# six4mix.net
KiCad netlist of a schematic drawn in EAGLE
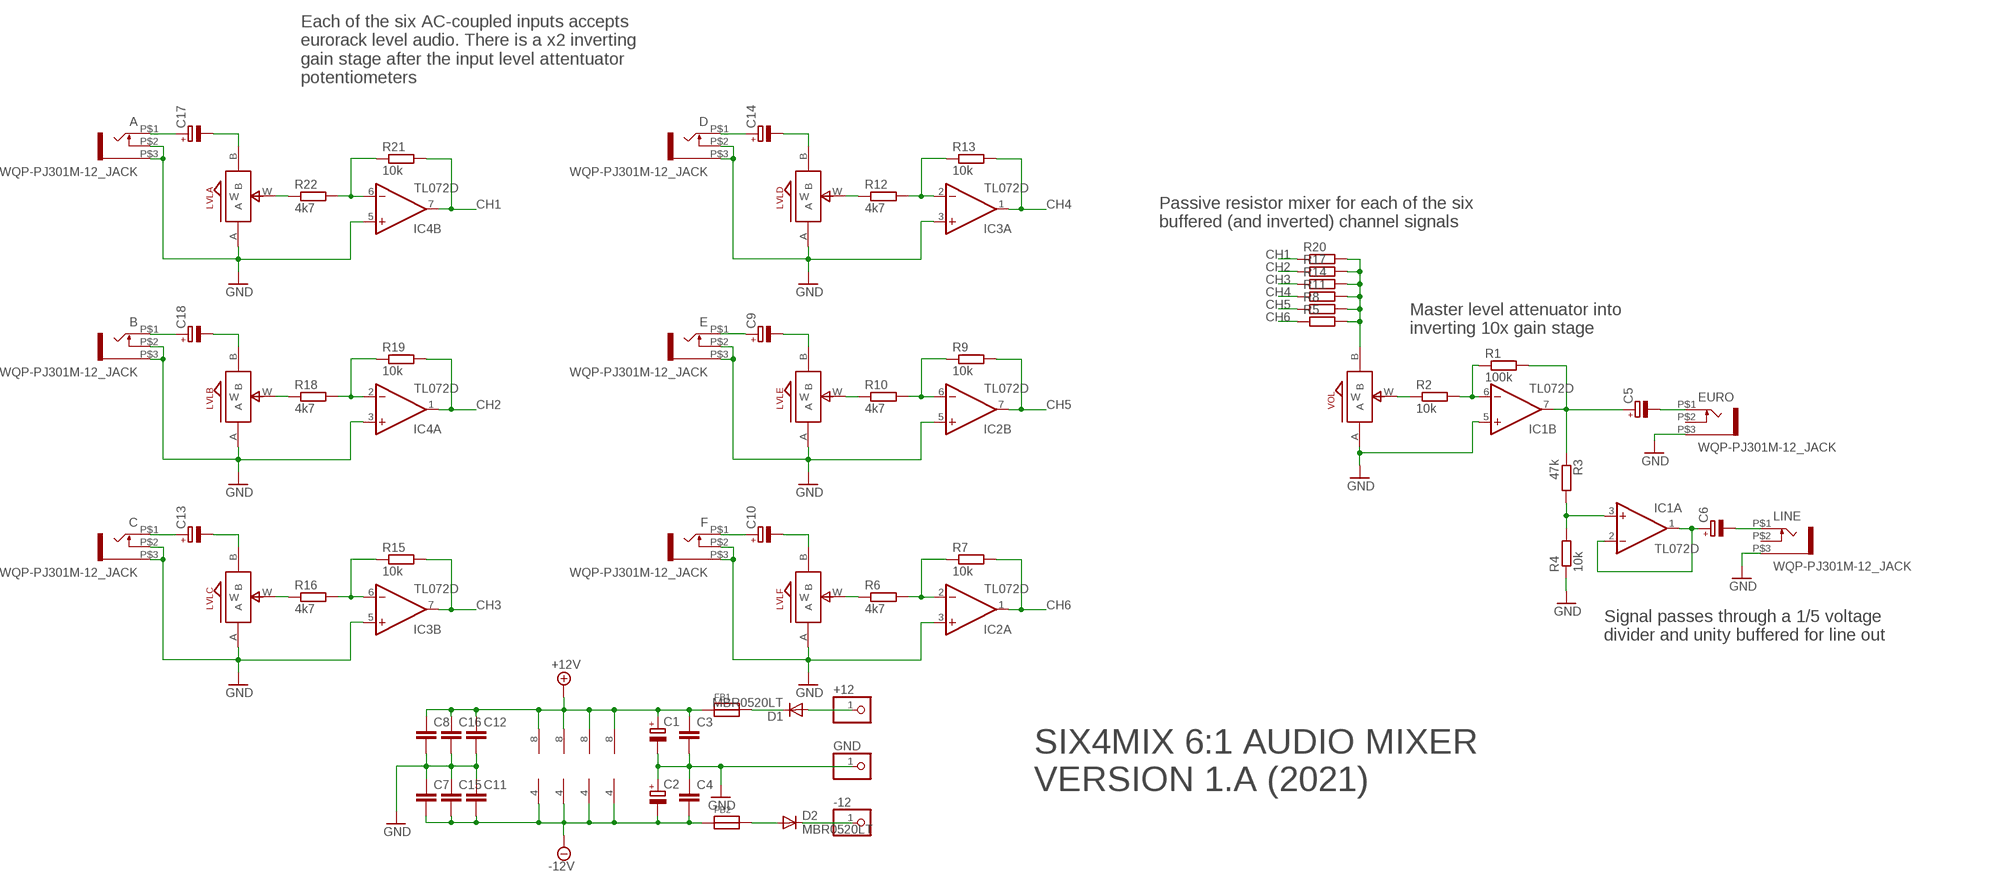
[diagram p0: schematic, sheet 1]

(export (version "E")
  (design (tool "Eeschema 10.0.6"))
  (components
    (comp (ref "+12")
      (value "PINHD-1X1")
      (footprint "eagle-import:1X01")
      (libsource (lib "eagle-import") (part "PINHD-1X1"))
    )
    (comp (ref "-12")
      (value "PINHD-1X1")
      (footprint "eagle-import:1X01")
      (libsource (lib "eagle-import") (part "PINHD-1X1"))
    )
    (comp (ref "A")
      (value "WQP-PJ301M-12_JACK")
      (footprint "eagle-import:WQP-PJ301M-12_JACK")
      (libsource (lib "eagle-import") (part "WQP-PJ301M-12_JACK"))
    )
    (comp (ref "B")
      (value "WQP-PJ301M-12_JACK")
      (footprint "eagle-import:WQP-PJ301M-12_JACK")
      (libsource (lib "eagle-import") (part "WQP-PJ301M-12_JACK"))
    )
    (comp (ref "C")
      (value "WQP-PJ301M-12_JACK")
      (footprint "eagle-import:WQP-PJ301M-12_JACK")
      (libsource (lib "eagle-import") (part "WQP-PJ301M-12_JACK"))
    )
    (comp (ref "C1")
      (value "CPOL-EUE2-4")
      (footprint "eagle-import:E2-4")
      (libsource (lib "eagle-import") (part "CPOL-EUE2-4"))
    )
    (comp (ref "C2")
      (value "CPOL-EUE2-4")
      (footprint "eagle-import:E2-4")
      (libsource (lib "eagle-import") (part "CPOL-EUE2-4"))
    )
    (comp (ref "C3")
      (value "C-EUC0805")
      (footprint "eagle-import:C0805")
      (libsource (lib "eagle-import") (part "C-EUC0805"))
    )
    (comp (ref "C4")
      (value "C-EUC0805")
      (footprint "eagle-import:C0805")
      (libsource (lib "eagle-import") (part "C-EUC0805"))
    )
    (comp (ref "C5")
      (value "CPOL-EUE2-4")
      (footprint "eagle-import:E2-4")
      (libsource (lib "eagle-import") (part "CPOL-EUE2-4"))
    )
    (comp (ref "C6")
      (value "CPOL-EUE2-4")
      (footprint "eagle-import:E2-4")
      (libsource (lib "eagle-import") (part "CPOL-EUE2-4"))
    )
    (comp (ref "C7")
      (value "C-EUC0805")
      (footprint "eagle-import:C0805")
      (libsource (lib "eagle-import") (part "C-EUC0805"))
    )
    (comp (ref "C8")
      (value "C-EUC0805")
      (footprint "eagle-import:C0805")
      (libsource (lib "eagle-import") (part "C-EUC0805"))
    )
    (comp (ref "C9")
      (value "CPOL-EUE2-4")
      (footprint "eagle-import:E2-4")
      (libsource (lib "eagle-import") (part "CPOL-EUE2-4"))
    )
    (comp (ref "C10")
      (value "CPOL-EUE2-4")
      (footprint "eagle-import:E2-4")
      (libsource (lib "eagle-import") (part "CPOL-EUE2-4"))
    )
    (comp (ref "C11")
      (value "C-EUC0805")
      (footprint "eagle-import:C0805")
      (libsource (lib "eagle-import") (part "C-EUC0805"))
    )
    (comp (ref "C12")
      (value "C-EUC0805")
      (footprint "eagle-import:C0805")
      (libsource (lib "eagle-import") (part "C-EUC0805"))
    )
    (comp (ref "C13")
      (value "CPOL-EUE2-4")
      (footprint "eagle-import:E2-4")
      (libsource (lib "eagle-import") (part "CPOL-EUE2-4"))
    )
    (comp (ref "C14")
      (value "CPOL-EUE2-4")
      (footprint "eagle-import:E2-4")
      (libsource (lib "eagle-import") (part "CPOL-EUE2-4"))
    )
    (comp (ref "C15")
      (value "C-EUC0805")
      (footprint "eagle-import:C0805")
      (libsource (lib "eagle-import") (part "C-EUC0805"))
    )
    (comp (ref "C16")
      (value "C-EUC0805")
      (footprint "eagle-import:C0805")
      (libsource (lib "eagle-import") (part "C-EUC0805"))
    )
    (comp (ref "C17")
      (value "CPOL-EUE2-4")
      (footprint "eagle-import:E2-4")
      (libsource (lib "eagle-import") (part "CPOL-EUE2-4"))
    )
    (comp (ref "C18")
      (value "CPOL-EUE2-4")
      (footprint "eagle-import:E2-4")
      (libsource (lib "eagle-import") (part "CPOL-EUE2-4"))
    )
    (comp (ref "D")
      (value "WQP-PJ301M-12_JACK")
      (footprint "eagle-import:WQP-PJ301M-12_JACK")
      (libsource (lib "eagle-import") (part "WQP-PJ301M-12_JACK"))
    )
    (comp (ref "D1")
      (value "MBR0520LT")
      (footprint "eagle-import:SOD123")
      (libsource (lib "eagle-import") (part "MBR0520LT"))
    )
    (comp (ref "D2")
      (value "MBR0520LT")
      (footprint "eagle-import:SOD123")
      (libsource (lib "eagle-import") (part "MBR0520LT"))
    )
    (comp (ref "E")
      (value "WQP-PJ301M-12_JACK")
      (footprint "eagle-import:WQP-PJ301M-12_JACK")
      (libsource (lib "eagle-import") (part "WQP-PJ301M-12_JACK"))
    )
    (comp (ref "EURO")
      (value "WQP-PJ301M-12_JACK")
      (footprint "eagle-import:WQP-PJ301M-12_JACK")
      (libsource (lib "eagle-import") (part "WQP-PJ301M-12_JACK"))
    )
    (comp (ref "F")
      (value "WQP-PJ301M-12_JACK")
      (footprint "eagle-import:WQP-PJ301M-12_JACK")
      (libsource (lib "eagle-import") (part "WQP-PJ301M-12_JACK"))
    )
    (comp (ref "FB1")
      (value "FERRITE")
      (footprint "eagle-import:0603")
      (libsource (lib "eagle-import") (part "FERRITE"))
    )
    (comp (ref "FB2")
      (value "FERRITE")
      (footprint "eagle-import:0603")
      (libsource (lib "eagle-import") (part "FERRITE"))
    )
    (comp (ref "GND")
      (value "PINHD-1X1")
      (footprint "eagle-import:1X01")
      (libsource (lib "eagle-import") (part "PINHD-1X1"))
    )
    (comp (ref "IC1")
      (value "TL072D")
      (footprint "eagle-import:SO08")
      (libsource (lib "eagle-import") (part "TL072D"))
    )
    (comp (ref "IC2")
      (value "TL072D")
      (footprint "eagle-import:SO08")
      (libsource (lib "eagle-import") (part "TL072D"))
    )
    (comp (ref "IC3")
      (value "TL072D")
      (footprint "eagle-import:SO08")
      (libsource (lib "eagle-import") (part "TL072D"))
    )
    (comp (ref "IC4")
      (value "TL072D")
      (footprint "eagle-import:SO08")
      (libsource (lib "eagle-import") (part "TL072D"))
    )
    (comp (ref "LINE")
      (value "WQP-PJ301M-12_JACK")
      (footprint "eagle-import:WQP-PJ301M-12_JACK")
      (libsource (lib "eagle-import") (part "WQP-PJ301M-12_JACK"))
    )
    (comp (ref "LVLA")
      (value "ALPS_POT_SMALL")
      (footprint "eagle-import:SMALL_ALPS_POT")
      (libsource (lib "eagle-import") (part "ALPS_POT_SMALL"))
    )
    (comp (ref "LVLB")
      (value "ALPS_POT_SMALL")
      (footprint "eagle-import:SMALL_ALPS_POT")
      (libsource (lib "eagle-import") (part "ALPS_POT_SMALL"))
    )
    (comp (ref "LVLC")
      (value "ALPS_POT_SMALL")
      (footprint "eagle-import:SMALL_ALPS_POT")
      (libsource (lib "eagle-import") (part "ALPS_POT_SMALL"))
    )
    (comp (ref "LVLD")
      (value "ALPS_POT_SMALL")
      (footprint "eagle-import:SMALL_ALPS_POT")
      (libsource (lib "eagle-import") (part "ALPS_POT_SMALL"))
    )
    (comp (ref "LVLE")
      (value "ALPS_POT_SMALL")
      (footprint "eagle-import:SMALL_ALPS_POT")
      (libsource (lib "eagle-import") (part "ALPS_POT_SMALL"))
    )
    (comp (ref "LVLF")
      (value "ALPS_POT_SMALL")
      (footprint "eagle-import:SMALL_ALPS_POT")
      (libsource (lib "eagle-import") (part "ALPS_POT_SMALL"))
    )
    (comp (ref "R1")
      (value "100k")
      (footprint "eagle-import:R0805")
      (libsource (lib "eagle-import") (part "R-EU_R0805"))
    )
    (comp (ref "R2")
      (value "10k")
      (footprint "eagle-import:R0805")
      (libsource (lib "eagle-import") (part "R-EU_R0805"))
    )
    (comp (ref "R3")
      (value "47k")
      (footprint "eagle-import:R0805")
      (libsource (lib "eagle-import") (part "R-EU_R0805"))
    )
    (comp (ref "R4")
      (value "10k")
      (footprint "eagle-import:R0805")
      (libsource (lib "eagle-import") (part "R-EU_R0805"))
    )
    (comp (ref "R5")
      (value "R-EU_R0805")
      (footprint "eagle-import:R0805")
      (libsource (lib "eagle-import") (part "R-EU_R0805"))
    )
    (comp (ref "R6")
      (value "4k7")
      (footprint "eagle-import:R0805")
      (libsource (lib "eagle-import") (part "R-EU_R0805"))
    )
    (comp (ref "R7")
      (value "10k")
      (footprint "eagle-import:R0805")
      (libsource (lib "eagle-import") (part "R-EU_R0805"))
    )
    (comp (ref "R8")
      (value "R-EU_R0805")
      (footprint "eagle-import:R0805")
      (libsource (lib "eagle-import") (part "R-EU_R0805"))
    )
    (comp (ref "R9")
      (value "10k")
      (footprint "eagle-import:R0805")
      (libsource (lib "eagle-import") (part "R-EU_R0805"))
    )
    (comp (ref "R10")
      (value "4k7")
      (footprint "eagle-import:R0805")
      (libsource (lib "eagle-import") (part "R-EU_R0805"))
    )
    (comp (ref "R11")
      (value "R-EU_R0805")
      (footprint "eagle-import:R0805")
      (libsource (lib "eagle-import") (part "R-EU_R0805"))
    )
    (comp (ref "R12")
      (value "4k7")
      (footprint "eagle-import:R0805")
      (libsource (lib "eagle-import") (part "R-EU_R0805"))
    )
    (comp (ref "R13")
      (value "10k")
      (footprint "eagle-import:R0805")
      (libsource (lib "eagle-import") (part "R-EU_R0805"))
    )
    (comp (ref "R14")
      (value "R-EU_R0805")
      (footprint "eagle-import:R0805")
      (libsource (lib "eagle-import") (part "R-EU_R0805"))
    )
    (comp (ref "R15")
      (value "10k")
      (footprint "eagle-import:R0805")
      (libsource (lib "eagle-import") (part "R-EU_R0805"))
    )
    (comp (ref "R16")
      (value "4k7")
      (footprint "eagle-import:R0805")
      (libsource (lib "eagle-import") (part "R-EU_R0805"))
    )
    (comp (ref "R17")
      (value "R-EU_R0805")
      (footprint "eagle-import:R0805")
      (libsource (lib "eagle-import") (part "R-EU_R0805"))
    )
    (comp (ref "R18")
      (value "4k7")
      (footprint "eagle-import:R0805")
      (libsource (lib "eagle-import") (part "R-EU_R0805"))
    )
    (comp (ref "R19")
      (value "10k")
      (footprint "eagle-import:R0805")
      (libsource (lib "eagle-import") (part "R-EU_R0805"))
    )
    (comp (ref "R20")
      (value "R-EU_R0805")
      (footprint "eagle-import:R0805")
      (libsource (lib "eagle-import") (part "R-EU_R0805"))
    )
    (comp (ref "R21")
      (value "10k")
      (footprint "eagle-import:R0805")
      (libsource (lib "eagle-import") (part "R-EU_R0805"))
    )
    (comp (ref "R22")
      (value "4k7")
      (footprint "eagle-import:R0805")
      (libsource (lib "eagle-import") (part "R-EU_R0805"))
    )
    (comp (ref "VOL")
      (value "ALPS_POT_SMALL")
      (footprint "eagle-import:SMALL_ALPS_POT")
      (libsource (lib "eagle-import") (part "ALPS_POT_SMALL"))
    )
  )
  (nets
    (net (code "1") (name "+12V") (class "Default")
      (node (ref "C1") (pin "+") (pinfunction "+_+") (pintype "passive"))
      (node (ref "C12") (pin "1") (pinfunction "1_1") (pintype "passive"))
      (node (ref "C16") (pin "1") (pinfunction "1_1") (pintype "passive"))
      (node (ref "C3") (pin "1") (pinfunction "1_1") (pintype "passive"))
      (node (ref "C8") (pin "1") (pinfunction "1_1") (pintype "passive"))
      (node (ref "FB1") (pin "1") (pinfunction "P$1_1") (pintype "bidirectional"))
      (node (ref "IC1") (pin "8") (pinfunction "V+_8") (pintype "power_in"))
      (node (ref "IC2") (pin "8") (pinfunction "V+_8") (pintype "power_in"))
      (node (ref "IC3") (pin "8") (pinfunction "V+_8") (pintype "power_in"))
      (node (ref "IC4") (pin "8") (pinfunction "V+_8") (pintype "power_in"))
    )
    (net (code "2") (name "-12V") (class "Default")
      (node (ref "C11") (pin "2") (pinfunction "2_2") (pintype "passive"))
      (node (ref "C15") (pin "2") (pinfunction "2_2") (pintype "passive"))
      (node (ref "C2") (pin "-") (pinfunction "-_-") (pintype "passive"))
      (node (ref "C4") (pin "2") (pinfunction "2_2") (pintype "passive"))
      (node (ref "C7") (pin "2") (pinfunction "2_2") (pintype "passive"))
      (node (ref "FB2") (pin "1") (pinfunction "P$1_1") (pintype "bidirectional"))
      (node (ref "IC1") (pin "4") (pinfunction "V-_4") (pintype "power_in"))
      (node (ref "IC2") (pin "4") (pinfunction "V-_4") (pintype "power_in"))
      (node (ref "IC3") (pin "4") (pinfunction "V-_4") (pintype "power_in"))
      (node (ref "IC4") (pin "4") (pinfunction "V-_4") (pintype "power_in"))
    )
    (net (code "3") (name "/CH1") (class "Default")
      (node (ref "IC4") (pin "7") (pinfunction "OUT_7") (pintype "output"))
      (node (ref "R20") (pin "1") (pinfunction "1_1") (pintype "passive"))
      (node (ref "R21") (pin "2") (pinfunction "2_2") (pintype "passive"))
    )
    (net (code "4") (name "/CH2") (class "Default")
      (node (ref "IC4") (pin "1") (pinfunction "OUT_1") (pintype "output"))
      (node (ref "R17") (pin "1") (pinfunction "1_1") (pintype "passive"))
      (node (ref "R19") (pin "2") (pinfunction "2_2") (pintype "passive"))
    )
    (net (code "5") (name "/CH3") (class "Default")
      (node (ref "IC3") (pin "7") (pinfunction "OUT_7") (pintype "output"))
      (node (ref "R14") (pin "1") (pinfunction "1_1") (pintype "passive"))
      (node (ref "R15") (pin "2") (pinfunction "2_2") (pintype "passive"))
    )
    (net (code "6") (name "/CH4") (class "Default")
      (node (ref "IC3") (pin "1") (pinfunction "OUT_1") (pintype "output"))
      (node (ref "R11") (pin "1") (pinfunction "1_1") (pintype "passive"))
      (node (ref "R13") (pin "2") (pinfunction "2_2") (pintype "passive"))
    )
    (net (code "7") (name "/CH5") (class "Default")
      (node (ref "IC2") (pin "7") (pinfunction "OUT_7") (pintype "output"))
      (node (ref "R8") (pin "1") (pinfunction "1_1") (pintype "passive"))
      (node (ref "R9") (pin "2") (pinfunction "2_2") (pintype "passive"))
    )
    (net (code "8") (name "/CH6") (class "Default")
      (node (ref "IC2") (pin "1") (pinfunction "OUT_1") (pintype "output"))
      (node (ref "R5") (pin "1") (pinfunction "1_1") (pintype "passive"))
      (node (ref "R7") (pin "2") (pinfunction "2_2") (pintype "passive"))
    )
    (net (code "9") (name "GND") (class "Default")
      (node (ref "A") (pin "P$2") (pinfunction "3_P$2") (pintype "passive"))
      (node (ref "A") (pin "P$3") (pinfunction "1_P$3") (pintype "passive"))
      (node (ref "B") (pin "P$2") (pinfunction "3_P$2") (pintype "passive"))
      (node (ref "B") (pin "P$3") (pinfunction "1_P$3") (pintype "passive"))
      (node (ref "C") (pin "P$2") (pinfunction "3_P$2") (pintype "passive"))
      (node (ref "C") (pin "P$3") (pinfunction "1_P$3") (pintype "passive"))
      (node (ref "C1") (pin "-") (pinfunction "-_-") (pintype "passive"))
      (node (ref "C11") (pin "1") (pinfunction "1_1") (pintype "passive"))
      (node (ref "C12") (pin "2") (pinfunction "2_2") (pintype "passive"))
      (node (ref "C15") (pin "1") (pinfunction "1_1") (pintype "passive"))
      (node (ref "C16") (pin "2") (pinfunction "2_2") (pintype "passive"))
      (node (ref "C2") (pin "+") (pinfunction "+_+") (pintype "passive"))
      (node (ref "C3") (pin "2") (pinfunction "2_2") (pintype "passive"))
      (node (ref "C4") (pin "1") (pinfunction "1_1") (pintype "passive"))
      (node (ref "C7") (pin "1") (pinfunction "1_1") (pintype "passive"))
      (node (ref "C8") (pin "2") (pinfunction "2_2") (pintype "passive"))
      (node (ref "D") (pin "P$2") (pinfunction "3_P$2") (pintype "passive"))
      (node (ref "D") (pin "P$3") (pinfunction "1_P$3") (pintype "passive"))
      (node (ref "E") (pin "P$2") (pinfunction "3_P$2") (pintype "passive"))
      (node (ref "E") (pin "P$3") (pinfunction "1_P$3") (pintype "passive"))
      (node (ref "EURO") (pin "P$3") (pinfunction "1_P$3") (pintype "passive"))
      (node (ref "F") (pin "P$2") (pinfunction "3_P$2") (pintype "passive"))
      (node (ref "F") (pin "P$3") (pinfunction "1_P$3") (pintype "passive"))
      (node (ref "GND") (pin "1") (pinfunction "1_1") (pintype "passive"))
      (node (ref "IC1") (pin "5") (pinfunction "+IN_5") (pintype "input"))
      (node (ref "IC2") (pin "3") (pinfunction "+IN_3") (pintype "input"))
      (node (ref "IC2") (pin "5") (pinfunction "+IN_5") (pintype "input"))
      (node (ref "IC3") (pin "3") (pinfunction "+IN_3") (pintype "input"))
      (node (ref "IC3") (pin "5") (pinfunction "+IN_5") (pintype "input"))
      (node (ref "IC4") (pin "3") (pinfunction "+IN_3") (pintype "input"))
      (node (ref "IC4") (pin "5") (pinfunction "+IN_5") (pintype "input"))
      (node (ref "LINE") (pin "P$3") (pinfunction "1_P$3") (pintype "passive"))
      (node (ref "LVLA") (pin "A") (pinfunction "A_A") (pintype "bidirectional"))
      (node (ref "LVLB") (pin "A") (pinfunction "A_A") (pintype "bidirectional"))
      (node (ref "LVLC") (pin "A") (pinfunction "A_A") (pintype "bidirectional"))
      (node (ref "LVLD") (pin "A") (pinfunction "A_A") (pintype "bidirectional"))
      (node (ref "LVLE") (pin "A") (pinfunction "A_A") (pintype "bidirectional"))
      (node (ref "LVLF") (pin "A") (pinfunction "A_A") (pintype "bidirectional"))
      (node (ref "R4") (pin "1") (pinfunction "1_1") (pintype "passive"))
      (node (ref "VOL") (pin "A") (pinfunction "A_A") (pintype "bidirectional"))
    )
    (net (code "10") (name "Net-(+12-Pad1)") (class "Default")
      (node (ref "+12") (pin "1") (pinfunction "1_1") (pintype "passive"))
      (node (ref "D1") (pin "A") (pinfunction "A_A") (pintype "passive"))
    )
    (net (code "11") (name "Net-(-12-Pad1)") (class "Default")
      (node (ref "-12") (pin "1") (pinfunction "1_1") (pintype "passive"))
      (node (ref "D2") (pin "C") (pinfunction "C_C") (pintype "passive"))
    )
    (net (code "12") (name "Net-(A-2)") (class "Default")
      (node (ref "A") (pin "P$1") (pinfunction "2_P$1") (pintype "passive"))
      (node (ref "C17") (pin "+") (pinfunction "+_+") (pintype "passive"))
    )
    (net (code "13") (name "Net-(B-2)") (class "Default")
      (node (ref "B") (pin "P$1") (pinfunction "2_P$1") (pintype "passive"))
      (node (ref "C18") (pin "+") (pinfunction "+_+") (pintype "passive"))
    )
    (net (code "14") (name "Net-(C-2)") (class "Default")
      (node (ref "C") (pin "P$1") (pinfunction "2_P$1") (pintype "passive"))
      (node (ref "C13") (pin "+") (pinfunction "+_+") (pintype "passive"))
    )
    (net (code "15") (name "Net-(C9-Pad-)") (class "Default")
      (node (ref "C9") (pin "-") (pinfunction "-_-") (pintype "passive"))
      (node (ref "LVLE") (pin "B") (pinfunction "B_B") (pintype "bidirectional"))
    )
    (net (code "16") (name "Net-(C10-Pad-)") (class "Default")
      (node (ref "C10") (pin "-") (pinfunction "-_-") (pintype "passive"))
      (node (ref "LVLF") (pin "B") (pinfunction "B_B") (pintype "bidirectional"))
    )
    (net (code "17") (name "Net-(C13-Pad-)") (class "Default")
      (node (ref "C13") (pin "-") (pinfunction "-_-") (pintype "passive"))
      (node (ref "LVLC") (pin "B") (pinfunction "B_B") (pintype "bidirectional"))
    )
    (net (code "18") (name "Net-(C14-Pad-)") (class "Default")
      (node (ref "C14") (pin "-") (pinfunction "-_-") (pintype "passive"))
      (node (ref "LVLD") (pin "B") (pinfunction "B_B") (pintype "bidirectional"))
    )
    (net (code "19") (name "Net-(C17-Pad-)") (class "Default")
      (node (ref "C17") (pin "-") (pinfunction "-_-") (pintype "passive"))
      (node (ref "LVLA") (pin "B") (pinfunction "B_B") (pintype "bidirectional"))
    )
    (net (code "20") (name "Net-(C18-Pad-)") (class "Default")
      (node (ref "C18") (pin "-") (pinfunction "-_-") (pintype "passive"))
      (node (ref "LVLB") (pin "B") (pinfunction "B_B") (pintype "bidirectional"))
    )
    (net (code "21") (name "Net-(D-2)") (class "Default")
      (node (ref "C14") (pin "+") (pinfunction "+_+") (pintype "passive"))
      (node (ref "D") (pin "P$1") (pinfunction "2_P$1") (pintype "passive"))
    )
    (net (code "22") (name "Net-(E-2)") (class "Default")
      (node (ref "C9") (pin "+") (pinfunction "+_+") (pintype "passive"))
      (node (ref "E") (pin "P$1") (pinfunction "2_P$1") (pintype "passive"))
    )
    (net (code "23") (name "Net-(EURO-2)") (class "Default")
      (node (ref "C5") (pin "-") (pinfunction "-_-") (pintype "passive"))
      (node (ref "EURO") (pin "P$1") (pinfunction "2_P$1") (pintype "passive"))
    )
    (net (code "24") (name "Net-(F-2)") (class "Default")
      (node (ref "C10") (pin "+") (pinfunction "+_+") (pintype "passive"))
      (node (ref "F") (pin "P$1") (pinfunction "2_P$1") (pintype "passive"))
    )
    (net (code "25") (name "Net-(FB1-P$2)") (class "Default")
      (node (ref "D1") (pin "C") (pinfunction "C_C") (pintype "passive"))
      (node (ref "FB1") (pin "2") (pinfunction "P$2_2") (pintype "bidirectional"))
    )
    (net (code "26") (name "Net-(FB2-P$2)") (class "Default")
      (node (ref "D2") (pin "A") (pinfunction "A_A") (pintype "passive"))
      (node (ref "FB2") (pin "2") (pinfunction "P$2_2") (pintype "bidirectional"))
    )
    (net (code "27") (name "Net-(IC1A-+IN)") (class "Default")
      (node (ref "IC1") (pin "3") (pinfunction "+IN_3") (pintype "input"))
      (node (ref "R3") (pin "2") (pinfunction "2_2") (pintype "passive"))
      (node (ref "R4") (pin "2") (pinfunction "2_2") (pintype "passive"))
    )
    (net (code "28") (name "Net-(IC1A--IN)") (class "Default")
      (node (ref "C6") (pin "+") (pinfunction "+_+") (pintype "passive"))
      (node (ref "IC1") (pin "1") (pinfunction "OUT_1") (pintype "output"))
      (node (ref "IC1") (pin "2") (pinfunction "-IN_2") (pintype "input"))
    )
    (net (code "29") (name "Net-(IC1B--IN)") (class "Default")
      (node (ref "IC1") (pin "6") (pinfunction "-IN_6") (pintype "input"))
      (node (ref "R1") (pin "1") (pinfunction "1_1") (pintype "passive"))
      (node (ref "R2") (pin "2") (pinfunction "2_2") (pintype "passive"))
    )
    (net (code "30") (name "Net-(IC1B-OUT)") (class "Default")
      (node (ref "C5") (pin "+") (pinfunction "+_+") (pintype "passive"))
      (node (ref "IC1") (pin "7") (pinfunction "OUT_7") (pintype "output"))
      (node (ref "R1") (pin "2") (pinfunction "2_2") (pintype "passive"))
      (node (ref "R3") (pin "1") (pinfunction "1_1") (pintype "passive"))
    )
    (net (code "31") (name "Net-(IC2A--IN)") (class "Default")
      (node (ref "IC2") (pin "2") (pinfunction "-IN_2") (pintype "input"))
      (node (ref "R6") (pin "2") (pinfunction "2_2") (pintype "passive"))
      (node (ref "R7") (pin "1") (pinfunction "1_1") (pintype "passive"))
    )
    (net (code "32") (name "Net-(IC2B--IN)") (class "Default")
      (node (ref "IC2") (pin "6") (pinfunction "-IN_6") (pintype "input"))
      (node (ref "R10") (pin "2") (pinfunction "2_2") (pintype "passive"))
      (node (ref "R9") (pin "1") (pinfunction "1_1") (pintype "passive"))
    )
    (net (code "33") (name "Net-(IC3A--IN)") (class "Default")
      (node (ref "IC3") (pin "2") (pinfunction "-IN_2") (pintype "input"))
      (node (ref "R12") (pin "2") (pinfunction "2_2") (pintype "passive"))
      (node (ref "R13") (pin "1") (pinfunction "1_1") (pintype "passive"))
    )
    (net (code "34") (name "Net-(IC3B--IN)") (class "Default")
      (node (ref "IC3") (pin "6") (pinfunction "-IN_6") (pintype "input"))
      (node (ref "R15") (pin "1") (pinfunction "1_1") (pintype "passive"))
      (node (ref "R16") (pin "2") (pinfunction "2_2") (pintype "passive"))
    )
    (net (code "35") (name "Net-(IC4A--IN)") (class "Default")
      (node (ref "IC4") (pin "2") (pinfunction "-IN_2") (pintype "input"))
      (node (ref "R18") (pin "2") (pinfunction "2_2") (pintype "passive"))
      (node (ref "R19") (pin "1") (pinfunction "1_1") (pintype "passive"))
    )
    (net (code "36") (name "Net-(IC4B--IN)") (class "Default")
      (node (ref "IC4") (pin "6") (pinfunction "-IN_6") (pintype "input"))
      (node (ref "R21") (pin "1") (pinfunction "1_1") (pintype "passive"))
      (node (ref "R22") (pin "2") (pinfunction "2_2") (pintype "passive"))
    )
    (net (code "37") (name "Net-(LINE-2)") (class "Default")
      (node (ref "C6") (pin "-") (pinfunction "-_-") (pintype "passive"))
      (node (ref "LINE") (pin "P$1") (pinfunction "2_P$1") (pintype "passive"))
    )
    (net (code "38") (name "Net-(LVLA-PadW)") (class "Default")
      (node (ref "LVLA") (pin "W") (pinfunction "W_W") (pintype "bidirectional"))
      (node (ref "R22") (pin "1") (pinfunction "1_1") (pintype "passive"))
    )
    (net (code "39") (name "Net-(LVLB-PadW)") (class "Default")
      (node (ref "LVLB") (pin "W") (pinfunction "W_W") (pintype "bidirectional"))
      (node (ref "R18") (pin "1") (pinfunction "1_1") (pintype "passive"))
    )
    (net (code "40") (name "Net-(LVLC-PadW)") (class "Default")
      (node (ref "LVLC") (pin "W") (pinfunction "W_W") (pintype "bidirectional"))
      (node (ref "R16") (pin "1") (pinfunction "1_1") (pintype "passive"))
    )
    (net (code "41") (name "Net-(LVLD-PadW)") (class "Default")
      (node (ref "LVLD") (pin "W") (pinfunction "W_W") (pintype "bidirectional"))
      (node (ref "R12") (pin "1") (pinfunction "1_1") (pintype "passive"))
    )
    (net (code "42") (name "Net-(LVLE-PadW)") (class "Default")
      (node (ref "LVLE") (pin "W") (pinfunction "W_W") (pintype "bidirectional"))
      (node (ref "R10") (pin "1") (pinfunction "1_1") (pintype "passive"))
    )
    (net (code "43") (name "Net-(LVLF-PadW)") (class "Default")
      (node (ref "LVLF") (pin "W") (pinfunction "W_W") (pintype "bidirectional"))
      (node (ref "R6") (pin "1") (pinfunction "1_1") (pintype "passive"))
    )
    (net (code "44") (name "Net-(R2-Pad1)") (class "Default")
      (node (ref "R2") (pin "1") (pinfunction "1_1") (pintype "passive"))
      (node (ref "VOL") (pin "W") (pinfunction "W_W") (pintype "bidirectional"))
    )
    (net (code "45") (name "Net-(R11-Pad2)") (class "Default")
      (node (ref "R11") (pin "2") (pinfunction "2_2") (pintype "passive"))
      (node (ref "R14") (pin "2") (pinfunction "2_2") (pintype "passive"))
      (node (ref "R17") (pin "2") (pinfunction "2_2") (pintype "passive"))
      (node (ref "R20") (pin "2") (pinfunction "2_2") (pintype "passive"))
      (node (ref "R5") (pin "2") (pinfunction "2_2") (pintype "passive"))
      (node (ref "R8") (pin "2") (pinfunction "2_2") (pintype "passive"))
      (node (ref "VOL") (pin "B") (pinfunction "B_B") (pintype "bidirectional"))
    )
    (net (code "46") (name "unconnected-(EURO-3-PadP$2)") (class "Default")
      (node (ref "EURO") (pin "P$2") (pinfunction "3_P$2") (pintype "passive"))
    )
    (net (code "47") (name "unconnected-(LINE-3-PadP$2)") (class "Default")
      (node (ref "LINE") (pin "P$2") (pinfunction "3_P$2") (pintype "passive"))
    )
  )
)
